# smartGarden_ACT_Rev01.net
KiCad netlist of a schematic drawn in Altium Designer
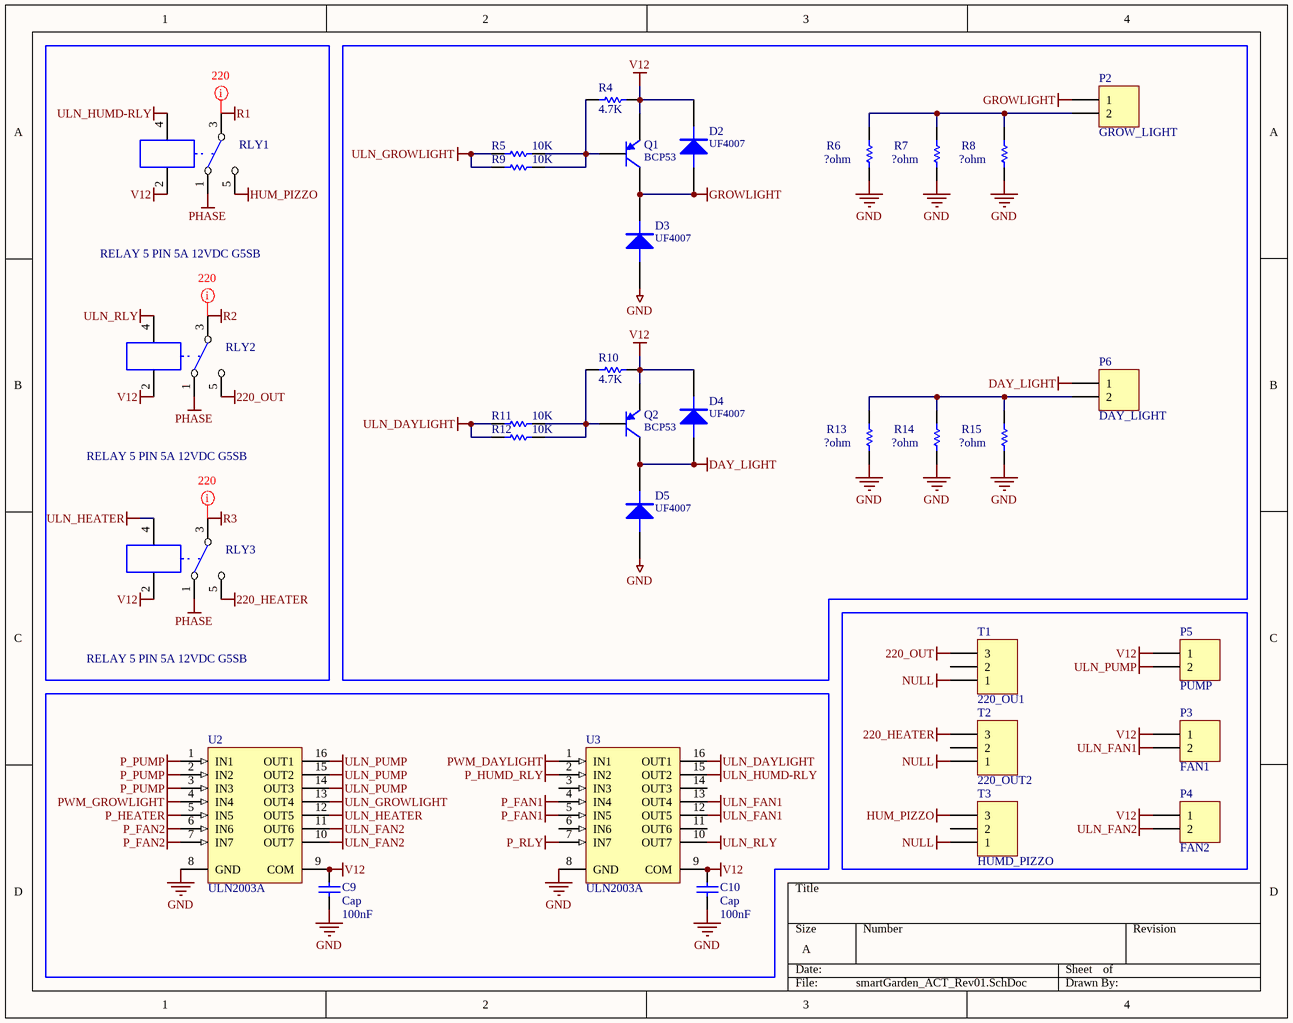
[diagram p0: smartGarden_ACT_Rev01.SchDoc]

(export (version "E")
  (design (tool "Eeschema 10.0.6"))
  (components
    (comp (ref "C9")
      (value "Cap")
      (footprint "0805_smd")
      (description "Capacitor")
      (fields (field (name "ALTIUM_VALUE") "100nF") (field (name "PUBLISHER") "Altium Limited"))
      (libsource (lib "Miscellaneous Devices") (part "Cap"))
    )
    (comp (ref "C10")
      (value "Cap")
      (footprint "0805_smd")
      (description "Capacitor")
      (fields (field (name "ALTIUM_VALUE") "100nF") (field (name "PUBLISHER") "Altium Limited"))
      (libsource (lib "Miscellaneous Devices") (part "Cap"))
    )
    (comp (ref "D2")
      (value "UF4007")
      (footprint "7227_SMD")
      (description "Diode")
      (libsource (lib "*") (part "DIODE"))
    )
    (comp (ref "D3")
      (value "UF4007")
      (footprint "7227_SMD")
      (description "Diode")
      (libsource (lib "*") (part "DIODE"))
    )
    (comp (ref "D4")
      (value "UF4007")
      (footprint "7227_SMD")
      (description "Diode")
      (libsource (lib "*") (part "DIODE"))
    )
    (comp (ref "D5")
      (value "UF4007")
      (footprint "7227_SMD")
      (description "Diode")
      (libsource (lib "*") (part "DIODE"))
    )
    (comp (ref "P2")
      (value "GROW_LIGHT")
      (footprint "PCON_L2")
      (description "Header, 2-Pin")
      (fields (field (name "PUBLISHER") "Altium Limited"))
      (libsource (lib "Miscellaneous Connectors") (part "Header 2"))
    )
    (comp (ref "P3")
      (value "FAN1")
      (footprint "CON2_XH")
      (description "Header, 2-Pin")
      (fields (field (name "PUBLISHER") "Altium Limited"))
      (libsource (lib "Miscellaneous Connectors") (part "Header 2"))
    )
    (comp (ref "P4")
      (value "FAN2")
      (footprint "CON2_XH")
      (description "Header, 2-Pin")
      (fields (field (name "PUBLISHER") "Altium Limited"))
      (libsource (lib "Miscellaneous Connectors") (part "Header 2"))
    )
    (comp (ref "P5")
      (value "PUMP")
      (footprint "CON2_XH")
      (description "Header, 2-Pin")
      (fields (field (name "PUBLISHER") "Altium Limited"))
      (libsource (lib "Miscellaneous Connectors") (part "Header 2"))
    )
    (comp (ref "P6")
      (value "DAY_LIGHT")
      (footprint "PCON_L2")
      (description "Header, 2-Pin")
      (fields (field (name "PUBLISHER") "Altium Limited"))
      (libsource (lib "Miscellaneous Connectors") (part "Header 2"))
    )
    (comp (ref "Q1") (value "BCP53") (footprint "SOT223") (libsource (lib "SchLib100") (part "2N3906")))
    (comp (ref "Q2") (value "BCP53") (footprint "SOT223") (libsource (lib "SchLib100") (part "2N3906")))
    (comp (ref "R4")
      (value "4.7K")
      (footprint "0805_smd")
      (description "Resistor")
      (fields (field (name "PUBLISHER") "Altium Limited"))
      (libsource (lib "MYLib496") (part "Res"))
    )
    (comp (ref "R5")
      (value "10K")
      (footprint "1206_SMD")
      (description "Resistor")
      (fields (field (name "PUBLISHER") "Altium Limited"))
      (libsource (lib "MYLib496") (part "Res"))
    )
    (comp (ref "R6")
      (value "?ohm")
      (footprint "0805_smd")
      (description "Resistor")
      (fields (field (name "Comment") "Res1") (field (name "PUBLISHER") "Altium Limited"))
      (libsource (lib "Miscellaneous Devices") (part "Res1"))
    )
    (comp (ref "R7")
      (value "?ohm")
      (footprint "0805_smd")
      (description "Resistor")
      (fields (field (name "Comment") "Res1") (field (name "PUBLISHER") "Altium Limited"))
      (libsource (lib "Miscellaneous Devices") (part "Res1"))
    )
    (comp (ref "R8")
      (value "?ohm")
      (footprint "0805_smd")
      (description "Resistor")
      (fields (field (name "Comment") "Res1") (field (name "PUBLISHER") "Altium Limited"))
      (libsource (lib "Miscellaneous Devices") (part "Res1"))
    )
    (comp (ref "R9")
      (value "10K")
      (footprint "1206_SMD")
      (description "Resistor")
      (fields (field (name "PUBLISHER") "Altium Limited"))
      (libsource (lib "MYLib496") (part "Res"))
    )
    (comp (ref "R10")
      (value "4.7K")
      (footprint "0805_smd")
      (description "Resistor")
      (fields (field (name "PUBLISHER") "Altium Limited"))
      (libsource (lib "MYLib496") (part "Res"))
    )
    (comp (ref "R11")
      (value "10K")
      (footprint "1206_SMD")
      (description "Resistor")
      (fields (field (name "PUBLISHER") "Altium Limited"))
      (libsource (lib "MYLib496") (part "Res"))
    )
    (comp (ref "R12")
      (value "10K")
      (footprint "1206_SMD")
      (description "Resistor")
      (fields (field (name "PUBLISHER") "Altium Limited"))
      (libsource (lib "MYLib496") (part "Res"))
    )
    (comp (ref "R13")
      (value "?ohm")
      (footprint "0805_smd")
      (description "Resistor")
      (fields (field (name "Comment") "Res1") (field (name "PUBLISHER") "Altium Limited"))
      (libsource (lib "Miscellaneous Devices") (part "Res1"))
    )
    (comp (ref "R14")
      (value "?ohm")
      (footprint "0805_smd")
      (description "Resistor")
      (fields (field (name "Comment") "Res1") (field (name "PUBLISHER") "Altium Limited"))
      (libsource (lib "Miscellaneous Devices") (part "Res1"))
    )
    (comp (ref "R15")
      (value "?ohm")
      (footprint "0805_smd")
      (description "Resistor")
      (fields (field (name "Comment") "Res1") (field (name "PUBLISHER") "Altium Limited"))
      (libsource (lib "Miscellaneous Devices") (part "Res1"))
    )
    (comp (ref "RLY1")
      (value "RELAY 5 PIN 5A 12VDC G5SB")
      (footprint "RLY_G5S")
      (libsource (lib "*") (part "RELAY-SPDT"))
    )
    (comp (ref "RLY2")
      (value "RELAY 5 PIN 5A 12VDC G5SB")
      (footprint "RLY_G5S")
      (libsource (lib "*") (part "RELAY-SPDT"))
    )
    (comp (ref "RLY3")
      (value "RELAY 5 PIN 5A 12VDC G5SB")
      (footprint "RLY_G5S")
      (libsource (lib "*") (part "RELAY-SPDT"))
    )
    (comp (ref "T1")
      (value "220_OU1")
      (footprint "PCON_L3")
      (description "Header, 3-Pin")
      (fields (field (name "PUBLISHER") "Altium Limited"))
      (libsource (lib "Miscellaneous Connectors") (part "Header 3"))
    )
    (comp (ref "T2")
      (value "220_OUT2")
      (footprint "PCON_L3")
      (description "Header, 3-Pin")
      (fields (field (name "PUBLISHER") "Altium Limited"))
      (libsource (lib "Miscellaneous Connectors") (part "Header 3"))
    )
    (comp (ref "T3")
      (value "HUMD_PIZZO")
      (footprint "PCON_L3")
      (description "Header, 3-Pin")
      (fields (field (name "PUBLISHER") "Altium Limited"))
      (libsource (lib "Miscellaneous Connectors") (part "Header 3"))
    )
    (comp (ref "U2")
      (value "ULN2003A")
      (footprint "SO-16_smd")
      (description "High-Voltage, High-Current Darlington Array")
      (fields (field (name "PUBLISHER") "Altium Limited"))
      (libsource (lib "Allegro Interface Darlington Driver") (part "ULN2004A"))
    )
    (comp (ref "U3")
      (value "ULN2003A")
      (footprint "SO-16_smd")
      (description "High-Voltage, High-Current Darlington Array")
      (fields (field (name "PUBLISHER") "Altium Limited"))
      (libsource (lib "Allegro Interface Darlington Driver") (part "ULN2004A"))
    )
  )
  (nets
    (net (code "1") (name "220_HEATER") (class "Default")
      (node (ref "RLY3") (pin "5") (pinfunction "NO_5") (pintype "passive"))
      (node (ref "T2") (pin "3") (pinfunction "3_3") (pintype "passive"))
    )
    (net (code "2") (name "220_OUT") (class "Default")
      (node (ref "RLY2") (pin "5") (pinfunction "NO_5") (pintype "passive"))
      (node (ref "T1") (pin "3") (pinfunction "3_3") (pintype "passive"))
    )
    (net (code "3") (name "DAY_LIGHT") (class "Default")
      (node (ref "D4") (pin "A") (pinfunction "1_A") (pintype "passive"))
      (node (ref "D5") (pin "K") (pinfunction "2_K") (pintype "passive"))
      (node (ref "P6") (pin "1") (pinfunction "1_1") (pintype "passive"))
      (node (ref "Q2") (pin "2") (pinfunction "C_2") (pintype "passive"))
    )
    (net (code "4") (name "GND") (class "Default")
      (node (ref "C10") (pin "1") (pinfunction "1_1") (pintype "passive"))
      (node (ref "C9") (pin "1") (pinfunction "1_1") (pintype "passive"))
      (node (ref "D3") (pin "A") (pinfunction "1_A") (pintype "passive"))
      (node (ref "D5") (pin "A") (pinfunction "1_A") (pintype "passive"))
      (node (ref "R13") (pin "1") (pinfunction "1_1") (pintype "passive"))
      (node (ref "R14") (pin "1") (pinfunction "1_1") (pintype "passive"))
      (node (ref "R15") (pin "1") (pinfunction "1_1") (pintype "passive"))
      (node (ref "R6") (pin "1") (pinfunction "1_1") (pintype "passive"))
      (node (ref "R7") (pin "1") (pinfunction "1_1") (pintype "passive"))
      (node (ref "R8") (pin "1") (pinfunction "1_1") (pintype "passive"))
      (node (ref "U2") (pin "8") (pinfunction "GND_8") (pintype "power_in"))
      (node (ref "U3") (pin "8") (pinfunction "GND_8") (pintype "power_in"))
    )
    (net (code "5") (name "GROWLIGHT") (class "Default")
      (node (ref "D2") (pin "A") (pinfunction "1_A") (pintype "passive"))
      (node (ref "D3") (pin "K") (pinfunction "2_K") (pintype "passive"))
      (node (ref "P2") (pin "1") (pinfunction "1_1") (pintype "passive"))
      (node (ref "Q1") (pin "2") (pinfunction "C_2") (pintype "passive"))
    )
    (net (code "6") (name "HUM_PIZZO") (class "Default")
      (node (ref "RLY1") (pin "5") (pinfunction "NO_5") (pintype "passive"))
      (node (ref "T3") (pin "3") (pinfunction "3_3") (pintype "passive"))
    )
    (net (code "7") (name "NULL") (class "Default")
      (node (ref "T1") (pin "1") (pinfunction "1_1") (pintype "passive"))
      (node (ref "T2") (pin "1") (pinfunction "1_1") (pintype "passive"))
      (node (ref "T3") (pin "1") (pinfunction "1_1") (pintype "passive"))
    )
    (net (code "8") (name "Net-(P2-Pad2)") (class "Default")
      (node (ref "P2") (pin "2") (pinfunction "2_2") (pintype "passive"))
      (node (ref "R6") (pin "2") (pinfunction "2_2") (pintype "passive"))
      (node (ref "R7") (pin "2") (pinfunction "2_2") (pintype "passive"))
      (node (ref "R8") (pin "2") (pinfunction "2_2") (pintype "passive"))
    )
    (net (code "9") (name "Net-(P6-Pad2)") (class "Default")
      (node (ref "P6") (pin "2") (pinfunction "2_2") (pintype "passive"))
      (node (ref "R13") (pin "2") (pinfunction "2_2") (pintype "passive"))
      (node (ref "R14") (pin "2") (pinfunction "2_2") (pintype "passive"))
      (node (ref "R15") (pin "2") (pinfunction "2_2") (pintype "passive"))
    )
    (net (code "10") (name "Net-(Q1-B)") (class "Default")
      (node (ref "Q1") (pin "1") (pinfunction "B_1") (pintype "passive"))
      (node (ref "R4") (pin "2") (pinfunction "2_2") (pintype "passive"))
      (node (ref "R5") (pin "1") (pinfunction "1_1") (pintype "passive"))
      (node (ref "R9") (pin "1") (pinfunction "1_1") (pintype "passive"))
    )
    (net (code "11") (name "Net-(Q2-B)") (class "Default")
      (node (ref "Q2") (pin "1") (pinfunction "B_1") (pintype "passive"))
      (node (ref "R10") (pin "2") (pinfunction "2_2") (pintype "passive"))
      (node (ref "R11") (pin "1") (pinfunction "1_1") (pintype "passive"))
      (node (ref "R12") (pin "1") (pinfunction "1_1") (pintype "passive"))
    )
    (net (code "12") (name "PHASE") (class "Default")
      (node (ref "RLY1") (pin "1") (pinfunction "NC_1") (pintype "passive"))
      (node (ref "RLY2") (pin "1") (pinfunction "NC_1") (pintype "passive"))
      (node (ref "RLY3") (pin "1") (pinfunction "NC_1") (pintype "passive"))
    )
    (net (code "13") (name "PWM_DAYLIGHT") (class "Default")
      (node (ref "U3") (pin "1") (pinfunction "IN1_1") (pintype "input"))
    )
    (net (code "14") (name "PWM_GROWLIGHT") (class "Default")
      (node (ref "U2") (pin "4") (pinfunction "IN4_4") (pintype "input"))
    )
    (net (code "15") (name "P_FAN1") (class "Default")
      (node (ref "U3") (pin "4") (pinfunction "IN4_4") (pintype "input"))
      (node (ref "U3") (pin "5") (pinfunction "IN5_5") (pintype "input"))
    )
    (net (code "16") (name "P_FAN2") (class "Default")
      (node (ref "U2") (pin "6") (pinfunction "IN6_6") (pintype "input"))
      (node (ref "U2") (pin "7") (pinfunction "IN7_7") (pintype "input"))
    )
    (net (code "17") (name "P_HEATER") (class "Default")
      (node (ref "U2") (pin "5") (pinfunction "IN5_5") (pintype "input"))
    )
    (net (code "18") (name "P_HUMD_RLY") (class "Default")
      (node (ref "U3") (pin "2") (pinfunction "IN2_2") (pintype "input"))
    )
    (net (code "19") (name "P_PUMP") (class "Default")
      (node (ref "U2") (pin "1") (pinfunction "IN1_1") (pintype "input"))
      (node (ref "U2") (pin "2") (pinfunction "IN2_2") (pintype "input"))
      (node (ref "U2") (pin "3") (pinfunction "IN3_3") (pintype "input"))
    )
    (net (code "20") (name "P_RLY") (class "Default")
      (node (ref "U3") (pin "7") (pinfunction "IN7_7") (pintype "input"))
    )
    (net (code "21") (name "R1") (class "Default")
      (node (ref "RLY1") (pin "3") (pinfunction "COM_3") (pintype "passive"))
    )
    (net (code "22") (name "R2") (class "Default")
      (node (ref "RLY2") (pin "3") (pinfunction "COM_3") (pintype "passive"))
    )
    (net (code "23") (name "R3") (class "Default")
      (node (ref "RLY3") (pin "3") (pinfunction "COM_3") (pintype "passive"))
    )
    (net (code "24") (name "ULN_DAYLIGHT") (class "Default")
      (node (ref "R11") (pin "2") (pinfunction "2_2") (pintype "passive"))
      (node (ref "R12") (pin "2") (pinfunction "2_2") (pintype "passive"))
      (node (ref "U3") (pin "16") (pinfunction "OUT1_16") (pintype "open_collector"))
    )
    (net (code "25") (name "ULN_FAN1") (class "Default")
      (node (ref "P3") (pin "2") (pinfunction "2_2") (pintype "passive"))
      (node (ref "U3") (pin "12") (pinfunction "OUT5_12") (pintype "open_collector"))
      (node (ref "U3") (pin "13") (pinfunction "OUT4_13") (pintype "open_collector"))
    )
    (net (code "26") (name "ULN_FAN2") (class "Default")
      (node (ref "P4") (pin "2") (pinfunction "2_2") (pintype "passive"))
      (node (ref "U2") (pin "10") (pinfunction "OUT7_10") (pintype "open_collector"))
      (node (ref "U2") (pin "11") (pinfunction "OUT6_11") (pintype "open_collector"))
    )
    (net (code "27") (name "ULN_GROWLIGHT") (class "Default")
      (node (ref "R5") (pin "2") (pinfunction "2_2") (pintype "passive"))
      (node (ref "R9") (pin "2") (pinfunction "2_2") (pintype "passive"))
      (node (ref "U2") (pin "13") (pinfunction "OUT4_13") (pintype "open_collector"))
    )
    (net (code "28") (name "ULN_HEATER") (class "Default")
      (node (ref "RLY3") (pin "4") (pinfunction "B_4") (pintype "passive"))
      (node (ref "U2") (pin "12") (pinfunction "OUT5_12") (pintype "open_collector"))
    )
    (net (code "29") (name "ULN_HUMD-RLY") (class "Default")
      (node (ref "RLY1") (pin "4") (pinfunction "B_4") (pintype "passive"))
      (node (ref "U3") (pin "15") (pinfunction "OUT2_15") (pintype "open_collector"))
    )
    (net (code "30") (name "ULN_PUMP") (class "Default")
      (node (ref "P5") (pin "2") (pinfunction "2_2") (pintype "passive"))
      (node (ref "U2") (pin "14") (pinfunction "OUT3_14") (pintype "open_collector"))
      (node (ref "U2") (pin "15") (pinfunction "OUT2_15") (pintype "open_collector"))
      (node (ref "U2") (pin "16") (pinfunction "OUT1_16") (pintype "open_collector"))
    )
    (net (code "31") (name "ULN_RLY") (class "Default")
      (node (ref "RLY2") (pin "4") (pinfunction "B_4") (pintype "passive"))
      (node (ref "U3") (pin "10") (pinfunction "OUT7_10") (pintype "open_collector"))
    )
    (net (code "32") (name "V12") (class "Default")
      (node (ref "C10") (pin "2") (pinfunction "2_2") (pintype "passive"))
      (node (ref "C9") (pin "2") (pinfunction "2_2") (pintype "passive"))
      (node (ref "D2") (pin "K") (pinfunction "2_K") (pintype "passive"))
      (node (ref "D4") (pin "K") (pinfunction "2_K") (pintype "passive"))
      (node (ref "P3") (pin "1") (pinfunction "1_1") (pintype "passive"))
      (node (ref "P4") (pin "1") (pinfunction "1_1") (pintype "passive"))
      (node (ref "P5") (pin "1") (pinfunction "1_1") (pintype "passive"))
      (node (ref "Q1") (pin "3") (pinfunction "E_3") (pintype "passive"))
      (node (ref "Q2") (pin "3") (pinfunction "E_3") (pintype "passive"))
      (node (ref "R10") (pin "1") (pinfunction "1_1") (pintype "passive"))
      (node (ref "R4") (pin "1") (pinfunction "1_1") (pintype "passive"))
      (node (ref "RLY1") (pin "2") (pinfunction "A_2") (pintype "passive"))
      (node (ref "RLY2") (pin "2") (pinfunction "A_2") (pintype "passive"))
      (node (ref "RLY3") (pin "2") (pinfunction "A_2") (pintype "passive"))
      (node (ref "U2") (pin "9") (pinfunction "COM_9") (pintype "passive"))
      (node (ref "U3") (pin "9") (pinfunction "COM_9") (pintype "passive"))
    )
    (net (code "33") (name "unconnected-(T1-Pad2)") (class "Default")
      (node (ref "T1") (pin "2") (pinfunction "2_2") (pintype "passive"))
    )
    (net (code "34") (name "unconnected-(T2-Pad2)") (class "Default")
      (node (ref "T2") (pin "2") (pinfunction "2_2") (pintype "passive"))
    )
    (net (code "35") (name "unconnected-(T3-Pad2)") (class "Default")
      (node (ref "T3") (pin "2") (pinfunction "2_2") (pintype "passive"))
    )
    (net (code "36") (name "unconnected-(U3-IN3-Pad3)") (class "Default")
      (node (ref "U3") (pin "3") (pinfunction "IN3_3") (pintype "input"))
    )
    (net (code "37") (name "unconnected-(U3-IN6-Pad6)") (class "Default")
      (node (ref "U3") (pin "6") (pinfunction "IN6_6") (pintype "input"))
    )
    (net (code "38") (name "unconnected-(U3-OUT3-Pad14)") (class "Default")
      (node (ref "U3") (pin "14") (pinfunction "OUT3_14") (pintype "open_collector"))
    )
    (net (code "39") (name "unconnected-(U3-OUT6-Pad11)") (class "Default")
      (node (ref "U3") (pin "11") (pinfunction "OUT6_11") (pintype "open_collector"))
    )
  )
)
